# Carte_principale_v2.net
KiCad netlist of a schematic drawn in EAGLE
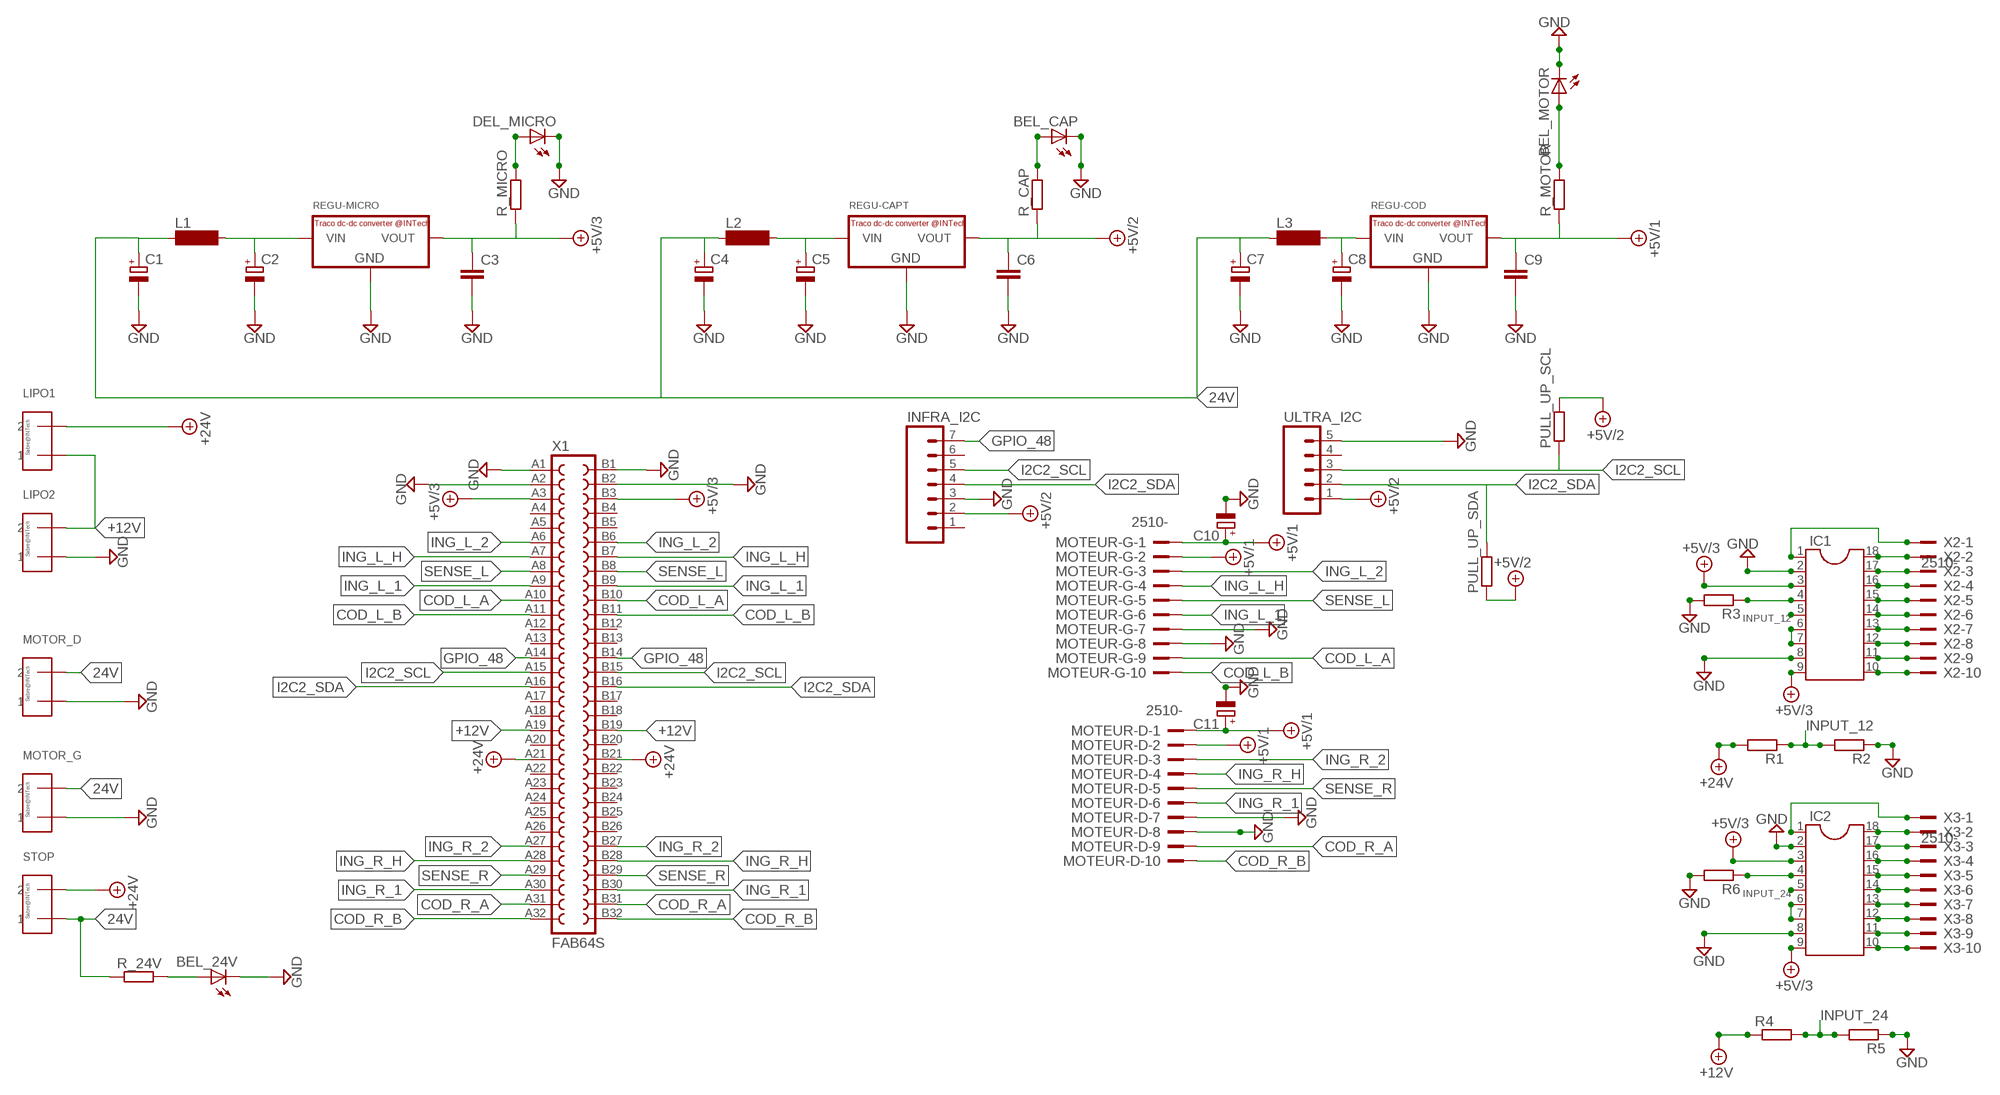
[diagram p0: schematic, sheet 1]

(export (version "E")
  (design (tool "Eeschema 10.0.6"))
  (components
    (comp (ref "BEL_24V")
      (value "LED5MM")
      (footprint "eagle-import:LED5MM")
      (libsource (lib "eagle-import") (part "LED5MM"))
    )
    (comp (ref "BEL_CAP")
      (value "LED5MM")
      (footprint "eagle-import:LED5MM")
      (libsource (lib "eagle-import") (part "LED5MM"))
    )
    (comp (ref "BEL_MOTOR")
      (value "LED5MM")
      (footprint "eagle-import:LED5MM")
      (libsource (lib "eagle-import") (part "LED5MM"))
    )
    (comp (ref "C1")
      (value "CPOL-EUE2.5-6")
      (footprint "eagle-import:E2,5-6")
      (libsource (lib "eagle-import") (part "CPOL-EUE2.5-6"))
    )
    (comp (ref "C2")
      (value "CPOL-EUE2.5-6")
      (footprint "eagle-import:E2,5-6")
      (libsource (lib "eagle-import") (part "CPOL-EUE2.5-6"))
    )
    (comp (ref "C3")
      (value "C-EU050-025X075")
      (footprint "eagle-import:C050-025X075")
      (libsource (lib "eagle-import") (part "C-EU050-025X075"))
    )
    (comp (ref "C4")
      (value "CPOL-EUE2.5-6")
      (footprint "eagle-import:E2,5-6")
      (libsource (lib "eagle-import") (part "CPOL-EUE2.5-6"))
    )
    (comp (ref "C5")
      (value "CPOL-EUE2.5-6")
      (footprint "eagle-import:E2,5-6")
      (libsource (lib "eagle-import") (part "CPOL-EUE2.5-6"))
    )
    (comp (ref "C6")
      (value "C-EU050-025X075")
      (footprint "eagle-import:C050-025X075")
      (libsource (lib "eagle-import") (part "C-EU050-025X075"))
    )
    (comp (ref "C7")
      (value "CPOL-EUE2.5-6")
      (footprint "eagle-import:E2,5-6")
      (libsource (lib "eagle-import") (part "CPOL-EUE2.5-6"))
    )
    (comp (ref "C8")
      (value "CPOL-EUE2.5-6")
      (footprint "eagle-import:E2,5-6")
      (libsource (lib "eagle-import") (part "CPOL-EUE2.5-6"))
    )
    (comp (ref "C9")
      (value "C5/3")
      (footprint "eagle-import:C5B3")
      (libsource (lib "eagle-import") (part "C5/3"))
    )
    (comp (ref "C10")
      (value "CPOL-EUE2.5-6")
      (footprint "eagle-import:E2,5-6")
      (libsource (lib "eagle-import") (part "CPOL-EUE2.5-6"))
    )
    (comp (ref "C11")
      (value "CPOL-EUE2.5-6")
      (footprint "eagle-import:E2,5-6")
      (libsource (lib "eagle-import") (part "CPOL-EUE2.5-6"))
    )
    (comp (ref "DEL_MICRO")
      (value "LED5MM")
      (footprint "eagle-import:LED5MM")
      (libsource (lib "eagle-import") (part "LED5MM"))
    )
    (comp (ref "IC1")
      (value "DIL18S")
      (footprint "eagle-import:SOCKET-18")
      (libsource (lib "eagle-import") (part "DIL18S"))
    )
    (comp (ref "IC2")
      (value "DIL18S")
      (footprint "eagle-import:SOCKET-18")
      (libsource (lib "eagle-import") (part "DIL18S"))
    )
    (comp (ref "INFRA_I2C")
      (value "M07")
      (footprint "eagle-import:07P")
      (libsource (lib "eagle-import") (part "M07"))
    )
    (comp (ref "L1")
      (value "SD12-1000")
      (footprint "eagle-import:SD12_1000")
      (libsource (lib "eagle-import") (part "SD12-1000"))
    )
    (comp (ref "L2")
      (value "SD12-1000")
      (footprint "eagle-import:SD12_1000")
      (libsource (lib "eagle-import") (part "SD12-1000"))
    )
    (comp (ref "L3")
      (value "SD12-1000")
      (footprint "eagle-import:SD12_1000")
      (libsource (lib "eagle-import") (part "SD12-1000"))
    )
    (comp (ref "LIPO1")
      (value "43160")
      (footprint "eagle-import:43160")
      (libsource (lib "eagle-import") (part "43160"))
    )
    (comp (ref "LIPO2")
      (value "43160")
      (footprint "eagle-import:43160")
      (libsource (lib "eagle-import") (part "43160"))
    )
    (comp (ref "MOTEUR-D")
      (value "2510-")
      (footprint "eagle-import:PAK100_2500-10")
      (fields (field (name "MF") "3M") (field (name "MPN") "2510-6002UB"))
      (libsource (lib "eagle-import") (part "2510-"))
    )
    (comp (ref "MOTEUR-G")
      (value "2510-")
      (footprint "eagle-import:PAK100_2500-10")
      (fields (field (name "MF") "3M") (field (name "MPN") "2510-6002UB"))
      (libsource (lib "eagle-import") (part "2510-"))
    )
    (comp (ref "MOTOR_D")
      (value "43160")
      (footprint "eagle-import:43160")
      (libsource (lib "eagle-import") (part "43160"))
    )
    (comp (ref "MOTOR_G")
      (value "43160")
      (footprint "eagle-import:43160")
      (libsource (lib "eagle-import") (part "43160"))
    )
    (comp (ref "PULL_UP_SCL")
      (value "R-EU_0204/7")
      (footprint "eagle-import:0204_7")
      (libsource (lib "eagle-import") (part "R-EU_0204/7"))
    )
    (comp (ref "PULL_UP_SDA")
      (value "R-EU_0204/7")
      (footprint "eagle-import:0204_7")
      (libsource (lib "eagle-import") (part "R-EU_0204/7"))
    )
    (comp (ref "R1")
      (value "R-EU_0204/7")
      (footprint "eagle-import:0204_7")
      (libsource (lib "eagle-import") (part "R-EU_0204/7"))
    )
    (comp (ref "R2")
      (value "R-EU_0204/7")
      (footprint "eagle-import:0204_7")
      (libsource (lib "eagle-import") (part "R-EU_0204/7"))
    )
    (comp (ref "R3")
      (value "R-EU_0204/7")
      (footprint "eagle-import:0204_7")
      (libsource (lib "eagle-import") (part "R-EU_0204/7"))
    )
    (comp (ref "R4")
      (value "R-EU_0204/7")
      (footprint "eagle-import:0204_7")
      (libsource (lib "eagle-import") (part "R-EU_0204/7"))
    )
    (comp (ref "R5")
      (value "R-EU_0204/7")
      (footprint "eagle-import:0204_7")
      (libsource (lib "eagle-import") (part "R-EU_0204/7"))
    )
    (comp (ref "R6")
      (value "R-EU_0204/7")
      (footprint "eagle-import:0204_7")
      (libsource (lib "eagle-import") (part "R-EU_0204/7"))
    )
    (comp (ref "REGU-CAPT")
      (value "R-78C-1.0_INTECH")
      (footprint "eagle-import:SIP3_INTECH")
      (libsource (lib "eagle-import") (part "R-78C-1.0_INTECH"))
    )
    (comp (ref "REGU-COD")
      (value "R-78C-1.0_INTECH")
      (footprint "eagle-import:SIP3_INTECH")
      (libsource (lib "eagle-import") (part "R-78C-1.0_INTECH"))
    )
    (comp (ref "REGU-MICRO")
      (value "R-78C-1.0_INTECH")
      (footprint "eagle-import:SIP3_INTECH")
      (libsource (lib "eagle-import") (part "R-78C-1.0_INTECH"))
    )
    (comp (ref "R_24V")
      (value "R-EU_0204/7")
      (footprint "eagle-import:0204_7")
      (libsource (lib "eagle-import") (part "R-EU_0204/7"))
    )
    (comp (ref "R_CAP")
      (value "R-EU_0204/7")
      (footprint "eagle-import:0204_7")
      (libsource (lib "eagle-import") (part "R-EU_0204/7"))
    )
    (comp (ref "R_MICRO")
      (value "R-EU_0204/7")
      (footprint "eagle-import:0204_7")
      (libsource (lib "eagle-import") (part "R-EU_0204/7"))
    )
    (comp (ref "R_MOTOR")
      (value "R-EU_0204/7")
      (footprint "eagle-import:0204_7")
      (libsource (lib "eagle-import") (part "R-EU_0204/7"))
    )
    (comp (ref "STOP")
      (value "43160")
      (footprint "eagle-import:43160")
      (libsource (lib "eagle-import") (part "43160"))
    )
    (comp (ref "ULTRA_I2C")
      (value "M05")
      (footprint "eagle-import:05P")
      (libsource (lib "eagle-import") (part "M05"))
    )
    (comp (ref "X1")
      (value "FAB64S")
      (footprint "eagle-import:FAB64S")
      (libsource (lib "eagle-import") (part "FAB64S"))
    )
    (comp (ref "X2")
      (value "2510-")
      (footprint "eagle-import:PAK100_2500-10")
      (fields (field (name "MF") "3M") (field (name "MPN") "2510-6002UB"))
      (libsource (lib "eagle-import") (part "2510-"))
    )
    (comp (ref "X3")
      (value "2510-")
      (footprint "eagle-import:PAK100_2500-10")
      (fields (field (name "MF") "3M") (field (name "MPN") "2510-6002UB"))
      (libsource (lib "eagle-import") (part "2510-"))
    )
  )
  (nets
    (net (code "1") (name "+5V{slash}1") (class "Default")
      (node (ref "C10") (pin "+") (pinfunction "+_+") (pintype "passive"))
      (node (ref "C11") (pin "+") (pinfunction "+_+") (pintype "passive"))
      (node (ref "C9") (pin "1") (pinfunction "1_1") (pintype "passive"))
      (node (ref "MOTEUR-D") (pin "1") (pinfunction "KL_1") (pintype "passive"))
      (node (ref "MOTEUR-D") (pin "2") (pinfunction "KL_2") (pintype "passive"))
      (node (ref "MOTEUR-G") (pin "1") (pinfunction "KL_1") (pintype "passive"))
      (node (ref "MOTEUR-G") (pin "2") (pinfunction "KL_2") (pintype "passive"))
      (node (ref "REGU-COD") (pin "VOUT") (pinfunction "VOUT_VOUT") (pintype "passive"))
      (node (ref "R_MOTOR") (pin "1") (pinfunction "1_1") (pintype "passive"))
    )
    (net (code "2") (name "+5V{slash}2") (class "Default")
      (node (ref "C6") (pin "1") (pinfunction "1_1") (pintype "passive"))
      (node (ref "INFRA_I2C") (pin "2") (pinfunction "2_2") (pintype "passive"))
      (node (ref "PULL_UP_SCL") (pin "2") (pinfunction "2_2") (pintype "passive"))
      (node (ref "PULL_UP_SDA") (pin "1") (pinfunction "1_1") (pintype "passive"))
      (node (ref "REGU-CAPT") (pin "VOUT") (pinfunction "VOUT_VOUT") (pintype "passive"))
      (node (ref "R_CAP") (pin "1") (pinfunction "1_1") (pintype "passive"))
      (node (ref "ULTRA_I2C") (pin "1") (pinfunction "1_1") (pintype "passive"))
    )
    (net (code "3") (name "+5V{slash}3") (class "Default")
      (node (ref "C3") (pin "1") (pinfunction "1_1") (pintype "passive"))
      (node (ref "IC1") (pin "3") (pinfunction "3_3") (pintype "passive"))
      (node (ref "IC1") (pin "9") (pinfunction "9_9") (pintype "passive"))
      (node (ref "IC2") (pin "3") (pinfunction "3_3") (pintype "passive"))
      (node (ref "IC2") (pin "9") (pinfunction "9_9") (pintype "passive"))
      (node (ref "REGU-MICRO") (pin "VOUT") (pinfunction "VOUT_VOUT") (pintype "passive"))
      (node (ref "R_MICRO") (pin "1") (pinfunction "1_1") (pintype "passive"))
      (node (ref "X1") (pin "A3") (pinfunction "A3_A3") (pintype "passive"))
      (node (ref "X1") (pin "B3") (pinfunction "B3_B3") (pintype "passive"))
    )
    (net (code "4") (name "+12V") (class "Default")
      (node (ref "LIPO1") (pin "1_1") (pinfunction "1_1_1") (pintype "bidirectional"))
      (node (ref "LIPO1") (pin "1_2") (pinfunction "1_1_2") (pintype "bidirectional"))
      (node (ref "LIPO2") (pin "2_1") (pinfunction "2_2_1") (pintype "bidirectional"))
      (node (ref "LIPO2") (pin "2_2") (pinfunction "2_2_2") (pintype "bidirectional"))
      (node (ref "R4") (pin "1") (pinfunction "1_1") (pintype "passive"))
      (node (ref "X1") (pin "A19") (pinfunction "A19_A19") (pintype "passive"))
      (node (ref "X1") (pin "B19") (pinfunction "B19_B19") (pintype "passive"))
    )
    (net (code "5") (name "+24V") (class "Default")
      (node (ref "LIPO1") (pin "2_1") (pinfunction "2_2_1") (pintype "bidirectional"))
      (node (ref "LIPO1") (pin "2_2") (pinfunction "2_2_2") (pintype "bidirectional"))
      (node (ref "R1") (pin "2") (pinfunction "2_2") (pintype "passive"))
      (node (ref "STOP") (pin "2_1") (pinfunction "2_2_1") (pintype "bidirectional"))
      (node (ref "STOP") (pin "2_2") (pinfunction "2_2_2") (pintype "bidirectional"))
      (node (ref "X1") (pin "A21") (pinfunction "A21_A21") (pintype "passive"))
      (node (ref "X1") (pin "B21") (pinfunction "B21_B21") (pintype "passive"))
    )
    (net (code "6") (name "/INPUT_12") (class "Default")
      (node (ref "IC1") (pin "5") (pinfunction "5_5") (pintype "passive"))
      (node (ref "R1") (pin "1") (pinfunction "1_1") (pintype "passive"))
      (node (ref "R2") (pin "2") (pinfunction "2_2") (pintype "passive"))
    )
    (net (code "7") (name "/INPUT_24") (class "Default")
      (node (ref "IC2") (pin "5") (pinfunction "5_5") (pintype "passive"))
      (node (ref "R4") (pin "2") (pinfunction "2_2") (pintype "passive"))
      (node (ref "R5") (pin "2") (pinfunction "2_2") (pintype "passive"))
    )
    (net (code "8") (name "24V") (class "Default")
      (node (ref "C1") (pin "+") (pinfunction "+_+") (pintype "passive"))
      (node (ref "C4") (pin "+") (pinfunction "+_+") (pintype "passive"))
      (node (ref "C7") (pin "+") (pinfunction "+_+") (pintype "passive"))
      (node (ref "L1") (pin "1") (pinfunction "1_1") (pintype "passive"))
      (node (ref "L2") (pin "1") (pinfunction "1_1") (pintype "passive"))
      (node (ref "L3") (pin "1") (pinfunction "1_1") (pintype "passive"))
      (node (ref "MOTOR_D") (pin "2_1") (pinfunction "2_2_1") (pintype "bidirectional"))
      (node (ref "MOTOR_D") (pin "2_2") (pinfunction "2_2_2") (pintype "bidirectional"))
      (node (ref "MOTOR_G") (pin "2_1") (pinfunction "2_2_1") (pintype "bidirectional"))
      (node (ref "MOTOR_G") (pin "2_2") (pinfunction "2_2_2") (pintype "bidirectional"))
      (node (ref "R_24V") (pin "1") (pinfunction "1_1") (pintype "passive"))
      (node (ref "STOP") (pin "1_1") (pinfunction "1_1_1") (pintype "bidirectional"))
      (node (ref "STOP") (pin "1_2") (pinfunction "1_1_2") (pintype "bidirectional"))
    )
    (net (code "9") (name "COD_L_A") (class "Default")
      (node (ref "MOTEUR-G") (pin "9") (pinfunction "KL_9") (pintype "passive"))
      (node (ref "X1") (pin "A10") (pinfunction "A10_A10") (pintype "passive"))
      (node (ref "X1") (pin "B10") (pinfunction "B10_B10") (pintype "passive"))
    )
    (net (code "10") (name "COD_L_B") (class "Default")
      (node (ref "MOTEUR-G") (pin "10") (pinfunction "KL_10") (pintype "passive"))
      (node (ref "X1") (pin "A11") (pinfunction "A11_A11") (pintype "passive"))
      (node (ref "X1") (pin "B11") (pinfunction "B11_B11") (pintype "passive"))
    )
    (net (code "11") (name "COD_R_A") (class "Default")
      (node (ref "MOTEUR-D") (pin "9") (pinfunction "KL_9") (pintype "passive"))
      (node (ref "X1") (pin "A31") (pinfunction "A31_A31") (pintype "passive"))
      (node (ref "X1") (pin "B31") (pinfunction "B31_B31") (pintype "passive"))
    )
    (net (code "12") (name "COD_R_B") (class "Default")
      (node (ref "MOTEUR-D") (pin "10") (pinfunction "KL_10") (pintype "passive"))
      (node (ref "X1") (pin "A32") (pinfunction "A32_A32") (pintype "passive"))
      (node (ref "X1") (pin "B32") (pinfunction "B32_B32") (pintype "passive"))
    )
    (net (code "13") (name "GND") (class "Default")
      (node (ref "BEL_24V") (pin "K") (pinfunction "C_K") (pintype "passive"))
      (node (ref "BEL_CAP") (pin "K") (pinfunction "C_K") (pintype "passive"))
      (node (ref "BEL_MOTOR") (pin "K") (pinfunction "C_K") (pintype "passive"))
      (node (ref "C1") (pin "-") (pinfunction "-_-") (pintype "passive"))
      (node (ref "C10") (pin "-") (pinfunction "-_-") (pintype "passive"))
      (node (ref "C11") (pin "-") (pinfunction "-_-") (pintype "passive"))
      (node (ref "C2") (pin "-") (pinfunction "-_-") (pintype "passive"))
      (node (ref "C3") (pin "2") (pinfunction "2_2") (pintype "passive"))
      (node (ref "C4") (pin "-") (pinfunction "-_-") (pintype "passive"))
      (node (ref "C5") (pin "-") (pinfunction "-_-") (pintype "passive"))
      (node (ref "C6") (pin "2") (pinfunction "2_2") (pintype "passive"))
      (node (ref "C7") (pin "-") (pinfunction "-_-") (pintype "passive"))
      (node (ref "C8") (pin "-") (pinfunction "-_-") (pintype "passive"))
      (node (ref "C9") (pin "2") (pinfunction "2_2") (pintype "passive"))
      (node (ref "DEL_MICRO") (pin "K") (pinfunction "C_K") (pintype "passive"))
      (node (ref "IC1") (pin "2") (pinfunction "2_2") (pintype "passive"))
      (node (ref "IC1") (pin "8") (pinfunction "8_8") (pintype "passive"))
      (node (ref "IC2") (pin "2") (pinfunction "2_2") (pintype "passive"))
      (node (ref "IC2") (pin "8") (pinfunction "8_8") (pintype "passive"))
      (node (ref "INFRA_I2C") (pin "3") (pinfunction "3_3") (pintype "passive"))
      (node (ref "LIPO2") (pin "1_1") (pinfunction "1_1_1") (pintype "bidirectional"))
      (node (ref "LIPO2") (pin "1_2") (pinfunction "1_1_2") (pintype "bidirectional"))
      (node (ref "MOTEUR-D") (pin "7") (pinfunction "KL_7") (pintype "passive"))
      (node (ref "MOTEUR-D") (pin "8") (pinfunction "KL_8") (pintype "passive"))
      (node (ref "MOTEUR-G") (pin "7") (pinfunction "KL_7") (pintype "passive"))
      (node (ref "MOTEUR-G") (pin "8") (pinfunction "KL_8") (pintype "passive"))
      (node (ref "MOTOR_D") (pin "1_1") (pinfunction "1_1_1") (pintype "bidirectional"))
      (node (ref "MOTOR_D") (pin "1_2") (pinfunction "1_1_2") (pintype "bidirectional"))
      (node (ref "MOTOR_G") (pin "1_1") (pinfunction "1_1_1") (pintype "bidirectional"))
      (node (ref "MOTOR_G") (pin "1_2") (pinfunction "1_1_2") (pintype "bidirectional"))
      (node (ref "R2") (pin "1") (pinfunction "1_1") (pintype "passive"))
      (node (ref "R3") (pin "2") (pinfunction "2_2") (pintype "passive"))
      (node (ref "R5") (pin "1") (pinfunction "1_1") (pintype "passive"))
      (node (ref "R6") (pin "2") (pinfunction "2_2") (pintype "passive"))
      (node (ref "REGU-CAPT") (pin "GND") (pinfunction "GND_GND") (pintype "passive"))
      (node (ref "REGU-COD") (pin "GND") (pinfunction "GND_GND") (pintype "passive"))
      (node (ref "REGU-MICRO") (pin "GND") (pinfunction "GND_GND") (pintype "passive"))
      (node (ref "ULTRA_I2C") (pin "5") (pinfunction "5_5") (pintype "passive"))
      (node (ref "X1") (pin "A1") (pinfunction "A1_A1") (pintype "passive"))
      (node (ref "X1") (pin "A2") (pinfunction "A2_A2") (pintype "passive"))
      (node (ref "X1") (pin "B1") (pinfunction "B1_B1") (pintype "passive"))
      (node (ref "X1") (pin "B2") (pinfunction "B2_B2") (pintype "passive"))
    )
    (net (code "14") (name "GPIO_48") (class "Default")
      (node (ref "INFRA_I2C") (pin "7") (pinfunction "7_7") (pintype "passive"))
      (node (ref "X1") (pin "A14") (pinfunction "A14_A14") (pintype "passive"))
      (node (ref "X1") (pin "B14") (pinfunction "B14_B14") (pintype "passive"))
    )
    (net (code "15") (name "I2C2_SCL") (class "Default")
      (node (ref "INFRA_I2C") (pin "5") (pinfunction "5_5") (pintype "passive"))
      (node (ref "PULL_UP_SCL") (pin "1") (pinfunction "1_1") (pintype "passive"))
      (node (ref "ULTRA_I2C") (pin "3") (pinfunction "3_3") (pintype "passive"))
      (node (ref "X1") (pin "A15") (pinfunction "A15_A15") (pintype "passive"))
      (node (ref "X1") (pin "B15") (pinfunction "B15_B15") (pintype "passive"))
    )
    (net (code "16") (name "I2C2_SDA") (class "Default")
      (node (ref "INFRA_I2C") (pin "4") (pinfunction "4_4") (pintype "passive"))
      (node (ref "PULL_UP_SDA") (pin "2") (pinfunction "2_2") (pintype "passive"))
      (node (ref "ULTRA_I2C") (pin "2") (pinfunction "2_2") (pintype "passive"))
      (node (ref "X1") (pin "A16") (pinfunction "A16_A16") (pintype "passive"))
      (node (ref "X1") (pin "B16") (pinfunction "B16_B16") (pintype "passive"))
    )
    (net (code "17") (name "ING_L_1") (class "Default")
      (node (ref "MOTEUR-G") (pin "6") (pinfunction "KL_6") (pintype "passive"))
      (node (ref "X1") (pin "A9") (pinfunction "A9_A9") (pintype "passive"))
      (node (ref "X1") (pin "B9") (pinfunction "B9_B9") (pintype "passive"))
    )
    (net (code "18") (name "ING_L_2") (class "Default")
      (node (ref "MOTEUR-G") (pin "3") (pinfunction "KL_3") (pintype "passive"))
      (node (ref "X1") (pin "A6") (pinfunction "A6_A6") (pintype "passive"))
      (node (ref "X1") (pin "B6") (pinfunction "B6_B6") (pintype "passive"))
    )
    (net (code "19") (name "ING_L_H") (class "Default")
      (node (ref "MOTEUR-G") (pin "4") (pinfunction "KL_4") (pintype "passive"))
      (node (ref "X1") (pin "A7") (pinfunction "A7_A7") (pintype "passive"))
      (node (ref "X1") (pin "B7") (pinfunction "B7_B7") (pintype "passive"))
    )
    (net (code "20") (name "ING_R_1") (class "Default")
      (node (ref "MOTEUR-D") (pin "6") (pinfunction "KL_6") (pintype "passive"))
      (node (ref "X1") (pin "A30") (pinfunction "A30_A30") (pintype "passive"))
      (node (ref "X1") (pin "B30") (pinfunction "B30_B30") (pintype "passive"))
    )
    (net (code "21") (name "ING_R_2") (class "Default")
      (node (ref "MOTEUR-D") (pin "3") (pinfunction "KL_3") (pintype "passive"))
      (node (ref "X1") (pin "A27") (pinfunction "A27_A27") (pintype "passive"))
      (node (ref "X1") (pin "B27") (pinfunction "B27_B27") (pintype "passive"))
    )
    (net (code "22") (name "ING_R_H") (class "Default")
      (node (ref "MOTEUR-D") (pin "4") (pinfunction "KL_4") (pintype "passive"))
      (node (ref "X1") (pin "A28") (pinfunction "A28_A28") (pintype "passive"))
      (node (ref "X1") (pin "B28") (pinfunction "B28_B28") (pintype "passive"))
    )
    (net (code "23") (name "Net-(BEL_24V-PadA)") (class "Default")
      (node (ref "BEL_24V") (pin "A") (pinfunction "A_A") (pintype "passive"))
      (node (ref "R_24V") (pin "2") (pinfunction "2_2") (pintype "passive"))
    )
    (net (code "24") (name "Net-(BEL_CAP-PadA)") (class "Default")
      (node (ref "BEL_CAP") (pin "A") (pinfunction "A_A") (pintype "passive"))
      (node (ref "R_CAP") (pin "2") (pinfunction "2_2") (pintype "passive"))
    )
    (net (code "25") (name "Net-(BEL_MOTOR-PadA)") (class "Default")
      (node (ref "BEL_MOTOR") (pin "A") (pinfunction "A_A") (pintype "passive"))
      (node (ref "R_MOTOR") (pin "2") (pinfunction "2_2") (pintype "passive"))
    )
    (net (code "26") (name "Net-(C2-Pad+)") (class "Default")
      (node (ref "C2") (pin "+") (pinfunction "+_+") (pintype "passive"))
      (node (ref "L1") (pin "2") (pinfunction "2_2") (pintype "passive"))
      (node (ref "REGU-MICRO") (pin "VIN") (pinfunction "VIN_VIN") (pintype "passive"))
    )
    (net (code "27") (name "Net-(C5-Pad+)") (class "Default")
      (node (ref "C5") (pin "+") (pinfunction "+_+") (pintype "passive"))
      (node (ref "L2") (pin "2") (pinfunction "2_2") (pintype "passive"))
      (node (ref "REGU-CAPT") (pin "VIN") (pinfunction "VIN_VIN") (pintype "passive"))
    )
    (net (code "28") (name "Net-(C8-Pad+)") (class "Default")
      (node (ref "C8") (pin "+") (pinfunction "+_+") (pintype "passive"))
      (node (ref "L3") (pin "2") (pinfunction "2_2") (pintype "passive"))
      (node (ref "REGU-COD") (pin "VIN") (pinfunction "VIN_VIN") (pintype "passive"))
    )
    (net (code "29") (name "Net-(DEL_MICRO-PadA)") (class "Default")
      (node (ref "DEL_MICRO") (pin "A") (pinfunction "A_A") (pintype "passive"))
      (node (ref "R_MICRO") (pin "2") (pinfunction "2_2") (pintype "passive"))
    )
    (net (code "30") (name "Net-(IC1-Pad4)") (class "Default")
      (node (ref "IC1") (pin "4") (pinfunction "4_4") (pintype "passive"))
      (node (ref "R3") (pin "1") (pinfunction "1_1") (pintype "passive"))
    )
    (net (code "31") (name "Net-(IC1-Pad6)") (class "Default")
      (node (ref "IC1") (pin "6") (pinfunction "6_6") (pintype "passive"))
      (node (ref "IC1") (pin "7") (pinfunction "7_7") (pintype "passive"))
    )
    (net (code "32") (name "Net-(IC2-Pad4)") (class "Default")
      (node (ref "IC2") (pin "4") (pinfunction "4_4") (pintype "passive"))
      (node (ref "R6") (pin "1") (pinfunction "1_1") (pintype "passive"))
    )
    (net (code "33") (name "Net-(IC2-Pad6)") (class "Default")
      (node (ref "IC2") (pin "6") (pinfunction "6_6") (pintype "passive"))
      (node (ref "IC2") (pin "7") (pinfunction "7_7") (pintype "passive"))
    )
    (net (code "34") (name "Net-(X2A-KL)") (class "Default")
      (node (ref "IC1") (pin "1") (pinfunction "1_1") (pintype "passive"))
      (node (ref "X2") (pin "1") (pinfunction "KL_1") (pintype "passive"))
    )
    (net (code "35") (name "Net-(X2B-KL)") (class "Default")
      (node (ref "IC1") (pin "10") (pinfunction "10_10") (pintype "passive"))
      (node (ref "X2") (pin "10") (pinfunction "KL_10") (pintype "passive"))
    )
    (net (code "36") (name "Net-(X2C-KL)") (class "Default")
      (node (ref "IC1") (pin "18") (pinfunction "18_18") (pintype "passive"))
      (node (ref "X2") (pin "2") (pinfunction "KL_2") (pintype "passive"))
    )
    (net (code "37") (name "Net-(X2D-KL)") (class "Default")
      (node (ref "IC1") (pin "17") (pinfunction "17_17") (pintype "passive"))
      (node (ref "X2") (pin "3") (pinfunction "KL_3") (pintype "passive"))
    )
    (net (code "38") (name "Net-(X2E-KL)") (class "Default")
      (node (ref "IC1") (pin "16") (pinfunction "16_16") (pintype "passive"))
      (node (ref "X2") (pin "4") (pinfunction "KL_4") (pintype "passive"))
    )
    (net (code "39") (name "Net-(X2F-KL)") (class "Default")
      (node (ref "IC1") (pin "15") (pinfunction "15_15") (pintype "passive"))
      (node (ref "X2") (pin "5") (pinfunction "KL_5") (pintype "passive"))
    )
    (net (code "40") (name "Net-(X2G-KL)") (class "Default")
      (node (ref "IC1") (pin "14") (pinfunction "14_14") (pintype "passive"))
      (node (ref "X2") (pin "6") (pinfunction "KL_6") (pintype "passive"))
    )
    (net (code "41") (name "Net-(X2H-KL)") (class "Default")
      (node (ref "IC1") (pin "13") (pinfunction "13_13") (pintype "passive"))
      (node (ref "X2") (pin "7") (pinfunction "KL_7") (pintype "passive"))
    )
    (net (code "42") (name "Net-(X2I-KL)") (class "Default")
      (node (ref "IC1") (pin "12") (pinfunction "12_12") (pintype "passive"))
      (node (ref "X2") (pin "8") (pinfunction "KL_8") (pintype "passive"))
    )
    (net (code "43") (name "Net-(X2J-KL)") (class "Default")
      (node (ref "IC1") (pin "11") (pinfunction "11_11") (pintype "passive"))
      (node (ref "X2") (pin "9") (pinfunction "KL_9") (pintype "passive"))
    )
    (net (code "44") (name "Net-(X3A-KL)") (class "Default")
      (node (ref "IC2") (pin "1") (pinfunction "1_1") (pintype "passive"))
      (node (ref "X3") (pin "1") (pinfunction "KL_1") (pintype "passive"))
    )
    (net (code "45") (name "Net-(X3B-KL)") (class "Default")
      (node (ref "IC2") (pin "10") (pinfunction "10_10") (pintype "passive"))
      (node (ref "X3") (pin "10") (pinfunction "KL_10") (pintype "passive"))
    )
    (net (code "46") (name "Net-(X3C-KL)") (class "Default")
      (node (ref "IC2") (pin "18") (pinfunction "18_18") (pintype "passive"))
      (node (ref "X3") (pin "2") (pinfunction "KL_2") (pintype "passive"))
    )
    (net (code "47") (name "Net-(X3D-KL)") (class "Default")
      (node (ref "IC2") (pin "17") (pinfunction "17_17") (pintype "passive"))
      (node (ref "X3") (pin "3") (pinfunction "KL_3") (pintype "passive"))
    )
    (net (code "48") (name "Net-(X3E-KL)") (class "Default")
      (node (ref "IC2") (pin "16") (pinfunction "16_16") (pintype "passive"))
      (node (ref "X3") (pin "4") (pinfunction "KL_4") (pintype "passive"))
    )
    (net (code "49") (name "Net-(X3F-KL)") (class "Default")
      (node (ref "IC2") (pin "15") (pinfunction "15_15") (pintype "passive"))
      (node (ref "X3") (pin "5") (pinfunction "KL_5") (pintype "passive"))
    )
    (net (code "50") (name "Net-(X3G-KL)") (class "Default")
      (node (ref "IC2") (pin "14") (pinfunction "14_14") (pintype "passive"))
      (node (ref "X3") (pin "6") (pinfunction "KL_6") (pintype "passive"))
    )
    (net (code "51") (name "Net-(X3H-KL)") (class "Default")
      (node (ref "IC2") (pin "13") (pinfunction "13_13") (pintype "passive"))
      (node (ref "X3") (pin "7") (pinfunction "KL_7") (pintype "passive"))
    )
    (net (code "52") (name "Net-(X3I-KL)") (class "Default")
      (node (ref "IC2") (pin "12") (pinfunction "12_12") (pintype "passive"))
      (node (ref "X3") (pin "8") (pinfunction "KL_8") (pintype "passive"))
    )
    (net (code "53") (name "Net-(X3J-KL)") (class "Default")
      (node (ref "IC2") (pin "11") (pinfunction "11_11") (pintype "passive"))
      (node (ref "X3") (pin "9") (pinfunction "KL_9") (pintype "passive"))
    )
    (net (code "54") (name "SENSE_L") (class "Default")
      (node (ref "MOTEUR-G") (pin "5") (pinfunction "KL_5") (pintype "passive"))
      (node (ref "X1") (pin "A8") (pinfunction "A8_A8") (pintype "passive"))
      (node (ref "X1") (pin "B8") (pinfunction "B8_B8") (pintype "passive"))
    )
    (net (code "55") (name "SENSE_R") (class "Default")
      (node (ref "MOTEUR-D") (pin "5") (pinfunction "KL_5") (pintype "passive"))
      (node (ref "X1") (pin "A29") (pinfunction "A29_A29") (pintype "passive"))
      (node (ref "X1") (pin "B29") (pinfunction "B29_B29") (pintype "passive"))
    )
    (net (code "56") (name "unconnected-(INFRA_I2C-Pad1)") (class "Default")
      (node (ref "INFRA_I2C") (pin "1") (pinfunction "1_1") (pintype "passive"))
    )
    (net (code "57") (name "unconnected-(INFRA_I2C-Pad6)") (class "Default")
      (node (ref "INFRA_I2C") (pin "6") (pinfunction "6_6") (pintype "passive"))
    )
    (net (code "58") (name "unconnected-(ULTRA_I2C-Pad4)") (class "Default")
      (node (ref "ULTRA_I2C") (pin "4") (pinfunction "4_4") (pintype "passive"))
    )
    (net (code "59") (name "unconnected-(X1-PadA4)") (class "Default")
      (node (ref "X1") (pin "A4") (pinfunction "A4_A4") (pintype "passive"))
    )
    (net (code "60") (name "unconnected-(X1-PadA5)") (class "Default")
      (node (ref "X1") (pin "A5") (pinfunction "A5_A5") (pintype "passive"))
    )
    (net (code "61") (name "unconnected-(X1-PadA12)") (class "Default")
      (node (ref "X1") (pin "A12") (pinfunction "A12_A12") (pintype "passive"))
    )
    (net (code "62") (name "unconnected-(X1-PadA13)") (class "Default")
      (node (ref "X1") (pin "A13") (pinfunction "A13_A13") (pintype "passive"))
    )
    (net (code "63") (name "unconnected-(X1-PadA17)") (class "Default")
      (node (ref "X1") (pin "A17") (pinfunction "A17_A17") (pintype "passive"))
    )
    (net (code "64") (name "unconnected-(X1-PadA18)") (class "Default")
      (node (ref "X1") (pin "A18") (pinfunction "A18_A18") (pintype "passive"))
    )
    (net (code "65") (name "unconnected-(X1-PadA20)") (class "Default")
      (node (ref "X1") (pin "A20") (pinfunction "A20_A20") (pintype "passive"))
    )
    (net (code "66") (name "unconnected-(X1-PadA22)") (class "Default")
      (node (ref "X1") (pin "A22") (pinfunction "A22_A22") (pintype "passive"))
    )
    (net (code "67") (name "unconnected-(X1-PadA23)") (class "Default")
      (node (ref "X1") (pin "A23") (pinfunction "A23_A23") (pintype "passive"))
    )
    (net (code "68") (name "unconnected-(X1-PadA24)") (class "Default")
      (node (ref "X1") (pin "A24") (pinfunction "A24_A24") (pintype "passive"))
    )
    (net (code "69") (name "unconnected-(X1-PadA25)") (class "Default")
      (node (ref "X1") (pin "A25") (pinfunction "A25_A25") (pintype "passive"))
    )
    (net (code "70") (name "unconnected-(X1-PadA26)") (class "Default")
      (node (ref "X1") (pin "A26") (pinfunction "A26_A26") (pintype "passive"))
    )
    (net (code "71") (name "unconnected-(X1-PadB4)") (class "Default")
      (node (ref "X1") (pin "B4") (pinfunction "B4_B4") (pintype "passive"))
    )
    (net (code "72") (name "unconnected-(X1-PadB5)") (class "Default")
      (node (ref "X1") (pin "B5") (pinfunction "B5_B5") (pintype "passive"))
    )
    (net (code "73") (name "unconnected-(X1-PadB12)") (class "Default")
      (node (ref "X1") (pin "B12") (pinfunction "B12_B12") (pintype "passive"))
    )
    (net (code "74") (name "unconnected-(X1-PadB13)") (class "Default")
      (node (ref "X1") (pin "B13") (pinfunction "B13_B13") (pintype "passive"))
    )
    (net (code "75") (name "unconnected-(X1-PadB17)") (class "Default")
      (node (ref "X1") (pin "B17") (pinfunction "B17_B17") (pintype "passive"))
    )
    (net (code "76") (name "unconnected-(X1-PadB18)") (class "Default")
      (node (ref "X1") (pin "B18") (pinfunction "B18_B18") (pintype "passive"))
    )
    (net (code "77") (name "unconnected-(X1-PadB20)") (class "Default")
      (node (ref "X1") (pin "B20") (pinfunction "B20_B20") (pintype "passive"))
    )
    (net (code "78") (name "unconnected-(X1-PadB22)") (class "Default")
      (node (ref "X1") (pin "B22") (pinfunction "B22_B22") (pintype "passive"))
    )
    (net (code "79") (name "unconnected-(X1-PadB23)") (class "Default")
      (node (ref "X1") (pin "B23") (pinfunction "B23_B23") (pintype "passive"))
    )
    (net (code "80") (name "unconnected-(X1-PadB24)") (class "Default")
      (node (ref "X1") (pin "B24") (pinfunction "B24_B24") (pintype "passive"))
    )
    (net (code "81") (name "unconnected-(X1-PadB25)") (class "Default")
      (node (ref "X1") (pin "B25") (pinfunction "B25_B25") (pintype "passive"))
    )
    (net (code "82") (name "unconnected-(X1-PadB26)") (class "Default")
      (node (ref "X1") (pin "B26") (pinfunction "B26_B26") (pintype "passive"))
    )
  )
)
